# DCP.net
KiCad netlist of a schematic drawn in Altium Designer
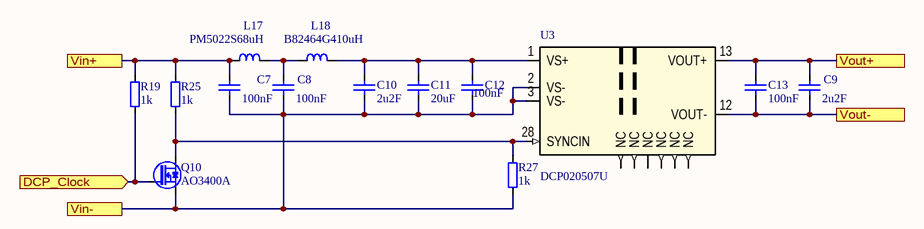
[diagram p0: DCP.SchDoc]

(export (version "E")
  (design (tool "Eeschema 10.0.6"))
  (components
    (comp (ref "C7")
      (value "100nF")
      (footprint "SMD0805CAP")
      (description "Чип конденсатор 0805")
      (fields (field (name "VOLTAGE") "25V") (field (name "TOLERANCE") "20%"))
      (libsource (lib "DDSintLib") (part "C0805"))
    )
    (comp (ref "C8")
      (value "100nF")
      (footprint "SMD0805CAP")
      (description "Чип конденсатор 0805")
      (fields (field (name "VOLTAGE") "25V") (field (name "TOLERANCE") "20%"))
      (libsource (lib "DDSintLib") (part "C0805"))
    )
    (comp (ref "C9")
      (value "2u2F")
      (footprint "SMD0805CAP")
      (description "Чип конденсатор 0805")
      (fields (field (name "VOLTAGE") "25V") (field (name "TOLERANCE") "20%"))
      (libsource (lib "DDSintLib") (part "C0805"))
    )
    (comp (ref "C10")
      (value "2u2F")
      (footprint "SMD0805CAP")
      (description "Чип конденсатор 0805")
      (fields (field (name "VOLTAGE") "25V") (field (name "TOLERANCE") "20%"))
      (libsource (lib "DDSintLib") (part "C0805"))
    )
    (comp (ref "C11")
      (value "20uF")
      (footprint "CAPC1206")
      (description "Чип конденсатор 0805")
      (fields (field (name "VOLTAGE") "16V") (field (name "TOLERANCE") "1%"))
      (libsource (lib "DDSintLib") (part "C1206"))
    )
    (comp (ref "C12")
      (value "100nF")
      (footprint "SMD0805CAP")
      (description "Чип конденсатор 0805")
      (fields (field (name "VOLTAGE") "25V") (field (name "TOLERANCE") "20%"))
      (libsource (lib "DDSintLib") (part "C0805"))
    )
    (comp (ref "C13")
      (value "100nF")
      (footprint "SMD0805CAP")
      (description "Чип конденсатор 0805")
      (fields (field (name "VOLTAGE") "25V") (field (name "TOLERANCE") "20%"))
      (libsource (lib "DDSintLib") (part "C0805"))
    )
    (comp (ref "L17")
      (value "PM5022S68uH")
      (footprint "IND_Bourns_PM5022S")
      (description "SMD Дроссель")
      (fields (field (name "VOLTAGE") "2") (field (name "TOLERANCE") "20%"))
      (libsource (lib "DDS1") (part "IND_BOURNS_PM5022S"))
    )
    (comp (ref "L18")
      (value "B82464G410uH")
      (footprint "IND_COILCRAFT_MSS1038")
      (description "SMD Дроссель")
      (fields (field (name "VOLTAGE") "2") (field (name "TOLERANCE") "20%"))
      (libsource (lib "DDSintLib") (part "B82464G4"))
    )
    (comp (ref "Q10")
      (value "AO3400A")
      (footprint "SOT95P229X119-3N")
      (description "NMOS")
      (fields (field (name "VOLTAGE") "30V"))
      (libsource (lib "DDSintLib") (part "AO3400A"))
    )
    (comp (ref "R19")
      (value "1k")
      (footprint "SMD0805RES")
      (description "Чип резистор 0805")
      (fields (field (name "TOLERANCE") "1%"))
      (libsource (lib "DDSintLib") (part "R0805"))
    )
    (comp (ref "R25")
      (value "1k")
      (footprint "SMD0805RES")
      (description "Чип резистор 0805")
      (fields (field (name "TOLERANCE") "1%"))
      (libsource (lib "DDSintLib") (part "R0805"))
    )
    (comp (ref "R27")
      (value "1k")
      (footprint "SMD0805RES")
      (description "Чип резистор 0805")
      (fields (field (name "TOLERANCE") "1%"))
      (libsource (lib "DDSintLib") (part "R0805"))
    )
    (comp (ref "U3")
      (value "DCP020507U")
      (footprint "SOIC127P1033X265-12_28N")
      (description "DC/DC xxV to isolated  yyV")
      (fields
        (field (name "VOLTAGE") "7V")
        (field (name "COPYRIGHT") "Copyright (C) 2022 Ultra Librarian. All rights reserved.")
      )
      (libsource (lib "DDS1") (part "DCP02xxyyU"))
    )
  )
  (nets
    (net (code "1") (name "/DCP_Clock") (class "Default")
      (node (ref "Q10") (pin "1") (pinfunction "G_1") (pintype "passive"))
      (node (ref "R19") (pin "2") (pinfunction "2_2") (pintype "passive"))
    )
    (net (code "2") (name "/Vin+") (class "Default")
      (node (ref "C7") (pin "2") (pinfunction "2_2") (pintype "passive"))
      (node (ref "L17") (pin "1") (pinfunction "1_1") (pintype "passive"))
      (node (ref "R19") (pin "1") (pinfunction "1_1") (pintype "passive"))
      (node (ref "R25") (pin "1") (pinfunction "1_1") (pintype "passive"))
    )
    (net (code "3") (name "/Vin-") (class "Default")
      (node (ref "C10") (pin "1") (pinfunction "1_1") (pintype "passive"))
      (node (ref "C11") (pin "1") (pinfunction "1_1") (pintype "passive"))
      (node (ref "C12") (pin "1") (pinfunction "1_1") (pintype "passive"))
      (node (ref "C7") (pin "1") (pinfunction "1_1") (pintype "passive"))
      (node (ref "C8") (pin "1") (pinfunction "1_1") (pintype "passive"))
      (node (ref "Q10") (pin "2") (pinfunction "S_2") (pintype "passive"))
      (node (ref "R27") (pin "2") (pinfunction "2_2") (pintype "passive"))
      (node (ref "U3") (pin "2") (pinfunction "VS-_2") (pintype "power_in"))
      (node (ref "U3") (pin "3") (pinfunction "VS-_3") (pintype "power_in"))
    )
    (net (code "4") (name "/Vout+") (class "Default")
      (node (ref "C13") (pin "2") (pinfunction "2_2") (pintype "passive"))
      (node (ref "C9") (pin "2") (pinfunction "2_2") (pintype "passive"))
      (node (ref "U3") (pin "13") (pinfunction "VOUT+_13") (pintype "power_in"))
    )
    (net (code "5") (name "/Vout-") (class "Default")
      (node (ref "C13") (pin "1") (pinfunction "1_1") (pintype "passive"))
      (node (ref "C9") (pin "1") (pinfunction "1_1") (pintype "passive"))
      (node (ref "U3") (pin "12") (pinfunction "VOUT-_12") (pintype "power_in"))
    )
    (net (code "6") (name "Net-(C8-Pad2)") (class "Default")
      (node (ref "C8") (pin "2") (pinfunction "2_2") (pintype "passive"))
      (node (ref "L17") (pin "2") (pinfunction "2_2") (pintype "passive"))
      (node (ref "L18") (pin "1") (pinfunction "1_1") (pintype "passive"))
    )
    (net (code "7") (name "Net-(Q10-D)") (class "Default")
      (node (ref "Q10") (pin "3") (pinfunction "D_3") (pintype "passive"))
      (node (ref "R25") (pin "2") (pinfunction "2_2") (pintype "passive"))
      (node (ref "R27") (pin "1") (pinfunction "1_1") (pintype "passive"))
      (node (ref "U3") (pin "28") (pinfunction "SYNCIN_28") (pintype "input"))
    )
    (net (code "8") (name "Net-(U3-VS+)") (class "Default")
      (node (ref "C10") (pin "2") (pinfunction "2_2") (pintype "passive"))
      (node (ref "C11") (pin "2") (pinfunction "2_2") (pintype "passive"))
      (node (ref "C12") (pin "2") (pinfunction "2_2") (pintype "passive"))
      (node (ref "L18") (pin "2") (pinfunction "2_2") (pintype "passive"))
      (node (ref "U3") (pin "1") (pinfunction "VS+_1") (pintype "power_in"))
    )
    (net (code "9") (name "unconnected-(U3-NC-Pad14)") (class "Default")
      (node (ref "U3") (pin "14") (pinfunction "NC_14") (pintype "output"))
    )
    (net (code "10") (name "unconnected-(U3-NC-Pad15)") (class "Default")
      (node (ref "U3") (pin "15") (pinfunction "NC_15") (pintype "output"))
    )
    (net (code "11") (name "unconnected-(U3-NC-Pad16)") (class "Default")
      (node (ref "U3") (pin "16") (pinfunction "NC_16") (pintype "passive"))
    )
    (net (code "12") (name "unconnected-(U3-NC-Pad17)") (class "Default")
      (node (ref "U3") (pin "17") (pinfunction "NC_17") (pintype "output"))
    )
    (net (code "13") (name "unconnected-(U3-NC-Pad26)") (class "Default")
      (node (ref "U3") (pin "26") (pinfunction "NC_26") (pintype "output"))
    )
    (net (code "14") (name "unconnected-(U3-NC-Pad27)") (class "Default")
      (node (ref "U3") (pin "27") (pinfunction "NC_27") (pintype "output"))
    )
  )
)
